# 20-AM64x-BootSelect.net
KiCad netlist of a schematic drawn in Altium Designer
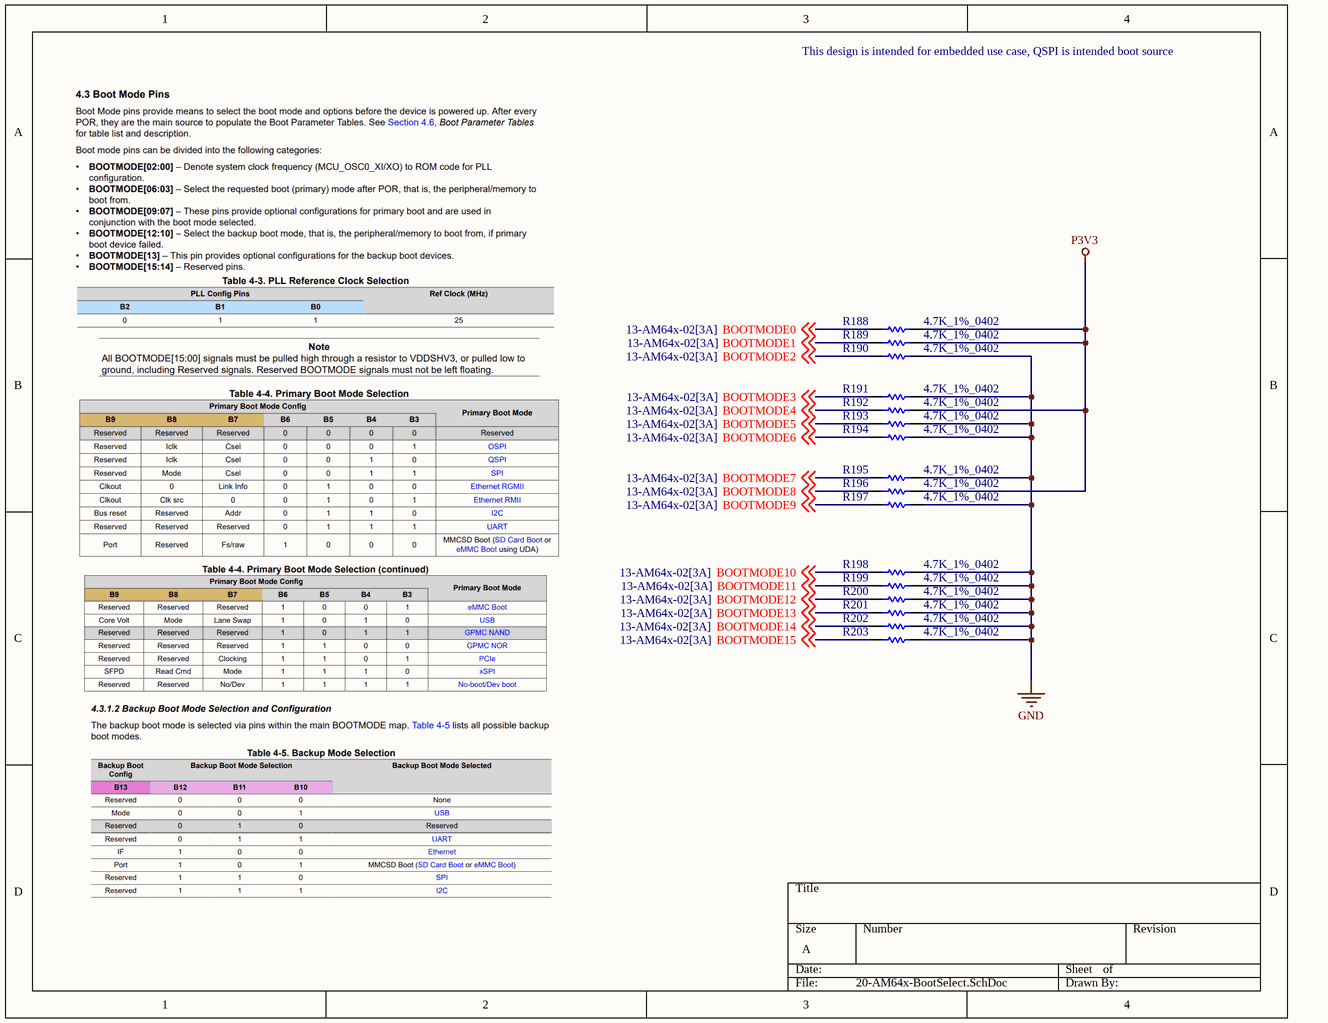
[diagram p0: 20-AM64x-BootSelect.SchDoc]

(export (version "E")
  (design (tool "Eeschema 10.0.6"))
  (components
    (comp (ref "R188")
      (value "4.7K_1%_0402")
      (footprint "RESC1005X40X25NL10T10")
      (fields (field (name "MANUFACTURER") "Bourns") (field (name "PART NUMBER") "CR0402-FX-4701GLF"))
      (libsource (lib "Altium Content Vault") (part "RES"))
    )
    (comp (ref "R189")
      (value "4.7K_1%_0402")
      (footprint "RESC1005X40X25NL10T10")
      (fields (field (name "MANUFACTURER") "Bourns") (field (name "PART NUMBER") "CR0402-FX-4701GLF"))
      (libsource (lib "Altium Content Vault") (part "RES"))
    )
    (comp (ref "R190")
      (value "4.7K_1%_0402")
      (footprint "RESC1005X40X25NL10T10")
      (fields (field (name "MANUFACTURER") "Bourns") (field (name "PART NUMBER") "CR0402-FX-4701GLF"))
      (libsource (lib "Altium Content Vault") (part "RES"))
    )
    (comp (ref "R191")
      (value "4.7K_1%_0402")
      (footprint "RESC1005X40X25NL10T10")
      (fields (field (name "MANUFACTURER") "Bourns") (field (name "PART NUMBER") "CR0402-FX-4701GLF"))
      (libsource (lib "Altium Content Vault") (part "RES"))
    )
    (comp (ref "R192")
      (value "4.7K_1%_0402")
      (footprint "RESC1005X40X25NL10T10")
      (fields (field (name "MANUFACTURER") "Bourns") (field (name "PART NUMBER") "CR0402-FX-4701GLF"))
      (libsource (lib "Altium Content Vault") (part "RES"))
    )
    (comp (ref "R193")
      (value "4.7K_1%_0402")
      (footprint "RESC1005X40X25NL10T10")
      (fields (field (name "MANUFACTURER") "Bourns") (field (name "PART NUMBER") "CR0402-FX-4701GLF"))
      (libsource (lib "Altium Content Vault") (part "RES"))
    )
    (comp (ref "R194")
      (value "4.7K_1%_0402")
      (footprint "RESC1005X40X25NL10T10")
      (fields (field (name "MANUFACTURER") "Bourns") (field (name "PART NUMBER") "CR0402-FX-4701GLF"))
      (libsource (lib "Altium Content Vault") (part "RES"))
    )
    (comp (ref "R195")
      (value "4.7K_1%_0402")
      (footprint "RESC1005X40X25NL10T10")
      (fields (field (name "MANUFACTURER") "Bourns") (field (name "PART NUMBER") "CR0402-FX-4701GLF"))
      (libsource (lib "Altium Content Vault") (part "RES"))
    )
    (comp (ref "R196")
      (value "4.7K_1%_0402")
      (footprint "RESC1005X40X25NL10T10")
      (fields (field (name "MANUFACTURER") "Bourns") (field (name "PART NUMBER") "CR0402-FX-4701GLF"))
      (libsource (lib "Altium Content Vault") (part "RES"))
    )
    (comp (ref "R197")
      (value "4.7K_1%_0402")
      (footprint "RESC1005X40X25NL10T10")
      (fields (field (name "MANUFACTURER") "Bourns") (field (name "PART NUMBER") "CR0402-FX-4701GLF"))
      (libsource (lib "Altium Content Vault") (part "RES"))
    )
    (comp (ref "R198")
      (value "4.7K_1%_0402")
      (footprint "RESC1005X40X25NL10T10")
      (fields (field (name "MANUFACTURER") "Bourns") (field (name "PART NUMBER") "CR0402-FX-4701GLF"))
      (libsource (lib "Altium Content Vault") (part "RES"))
    )
    (comp (ref "R199")
      (value "4.7K_1%_0402")
      (footprint "RESC1005X40X25NL10T10")
      (fields (field (name "MANUFACTURER") "Bourns") (field (name "PART NUMBER") "CR0402-FX-4701GLF"))
      (libsource (lib "Altium Content Vault") (part "RES"))
    )
    (comp (ref "R200")
      (value "4.7K_1%_0402")
      (footprint "RESC1005X40X25NL10T10")
      (fields (field (name "MANUFACTURER") "Bourns") (field (name "PART NUMBER") "CR0402-FX-4701GLF"))
      (libsource (lib "Altium Content Vault") (part "RES"))
    )
    (comp (ref "R201")
      (value "4.7K_1%_0402")
      (footprint "RESC1005X40X25NL10T10")
      (fields (field (name "MANUFACTURER") "Bourns") (field (name "PART NUMBER") "CR0402-FX-4701GLF"))
      (libsource (lib "Altium Content Vault") (part "RES"))
    )
    (comp (ref "R202")
      (value "4.7K_1%_0402")
      (footprint "RESC1005X40X25NL10T10")
      (fields (field (name "MANUFACTURER") "Bourns") (field (name "PART NUMBER") "CR0402-FX-4701GLF"))
      (libsource (lib "Altium Content Vault") (part "RES"))
    )
    (comp (ref "R203")
      (value "4.7K_1%_0402")
      (footprint "RESC1005X40X25NL10T10")
      (fields (field (name "MANUFACTURER") "Bourns") (field (name "PART NUMBER") "CR0402-FX-4701GLF"))
      (libsource (lib "Altium Content Vault") (part "RES"))
    )
  )
  (nets
    (net (code "1") (name "BOOTMODE0") (class "Default")
      (node (ref "R188") (pin "2") (pinfunction "2_2") (pintype "passive"))
    )
    (net (code "2") (name "BOOTMODE1") (class "Default")
      (node (ref "R189") (pin "2") (pinfunction "2_2") (pintype "passive"))
    )
    (net (code "3") (name "BOOTMODE2") (class "Default")
      (node (ref "R190") (pin "2") (pinfunction "2_2") (pintype "passive"))
    )
    (net (code "4") (name "BOOTMODE3") (class "Default")
      (node (ref "R191") (pin "2") (pinfunction "2_2") (pintype "passive"))
    )
    (net (code "5") (name "BOOTMODE4") (class "Default")
      (node (ref "R192") (pin "2") (pinfunction "2_2") (pintype "passive"))
    )
    (net (code "6") (name "BOOTMODE5") (class "Default")
      (node (ref "R193") (pin "2") (pinfunction "2_2") (pintype "passive"))
    )
    (net (code "7") (name "BOOTMODE6") (class "Default")
      (node (ref "R194") (pin "2") (pinfunction "2_2") (pintype "passive"))
    )
    (net (code "8") (name "BOOTMODE7") (class "Default")
      (node (ref "R195") (pin "2") (pinfunction "2_2") (pintype "passive"))
    )
    (net (code "9") (name "BOOTMODE8") (class "Default")
      (node (ref "R196") (pin "2") (pinfunction "2_2") (pintype "passive"))
    )
    (net (code "10") (name "BOOTMODE9") (class "Default")
      (node (ref "R197") (pin "2") (pinfunction "2_2") (pintype "passive"))
    )
    (net (code "11") (name "BOOTMODE10") (class "Default")
      (node (ref "R198") (pin "2") (pinfunction "2_2") (pintype "passive"))
    )
    (net (code "12") (name "BOOTMODE11") (class "Default")
      (node (ref "R199") (pin "2") (pinfunction "2_2") (pintype "passive"))
    )
    (net (code "13") (name "BOOTMODE12") (class "Default")
      (node (ref "R200") (pin "2") (pinfunction "2_2") (pintype "passive"))
    )
    (net (code "14") (name "BOOTMODE13") (class "Default")
      (node (ref "R201") (pin "2") (pinfunction "2_2") (pintype "passive"))
    )
    (net (code "15") (name "BOOTMODE14") (class "Default")
      (node (ref "R202") (pin "2") (pinfunction "2_2") (pintype "passive"))
    )
    (net (code "16") (name "BOOTMODE15") (class "Default")
      (node (ref "R203") (pin "2") (pinfunction "2_2") (pintype "passive"))
    )
    (net (code "17") (name "GND") (class "Default")
      (node (ref "R190") (pin "1") (pinfunction "1_1") (pintype "passive"))
      (node (ref "R191") (pin "1") (pinfunction "1_1") (pintype "passive"))
      (node (ref "R193") (pin "1") (pinfunction "1_1") (pintype "passive"))
      (node (ref "R194") (pin "1") (pinfunction "1_1") (pintype "passive"))
      (node (ref "R195") (pin "1") (pinfunction "1_1") (pintype "passive"))
      (node (ref "R197") (pin "1") (pinfunction "1_1") (pintype "passive"))
      (node (ref "R198") (pin "1") (pinfunction "1_1") (pintype "passive"))
      (node (ref "R199") (pin "1") (pinfunction "1_1") (pintype "passive"))
      (node (ref "R200") (pin "1") (pinfunction "1_1") (pintype "passive"))
      (node (ref "R201") (pin "1") (pinfunction "1_1") (pintype "passive"))
      (node (ref "R202") (pin "1") (pinfunction "1_1") (pintype "passive"))
      (node (ref "R203") (pin "1") (pinfunction "1_1") (pintype "passive"))
    )
    (net (code "18") (name "P3V3") (class "Default")
      (node (ref "R188") (pin "1") (pinfunction "1_1") (pintype "passive"))
      (node (ref "R189") (pin "1") (pinfunction "1_1") (pintype "passive"))
      (node (ref "R192") (pin "1") (pinfunction "1_1") (pintype "passive"))
      (node (ref "R196") (pin "1") (pinfunction "1_1") (pintype "passive"))
    )
  )
)
